# BRAINNEO.net
KiCad netlist of a schematic drawn in EAGLE
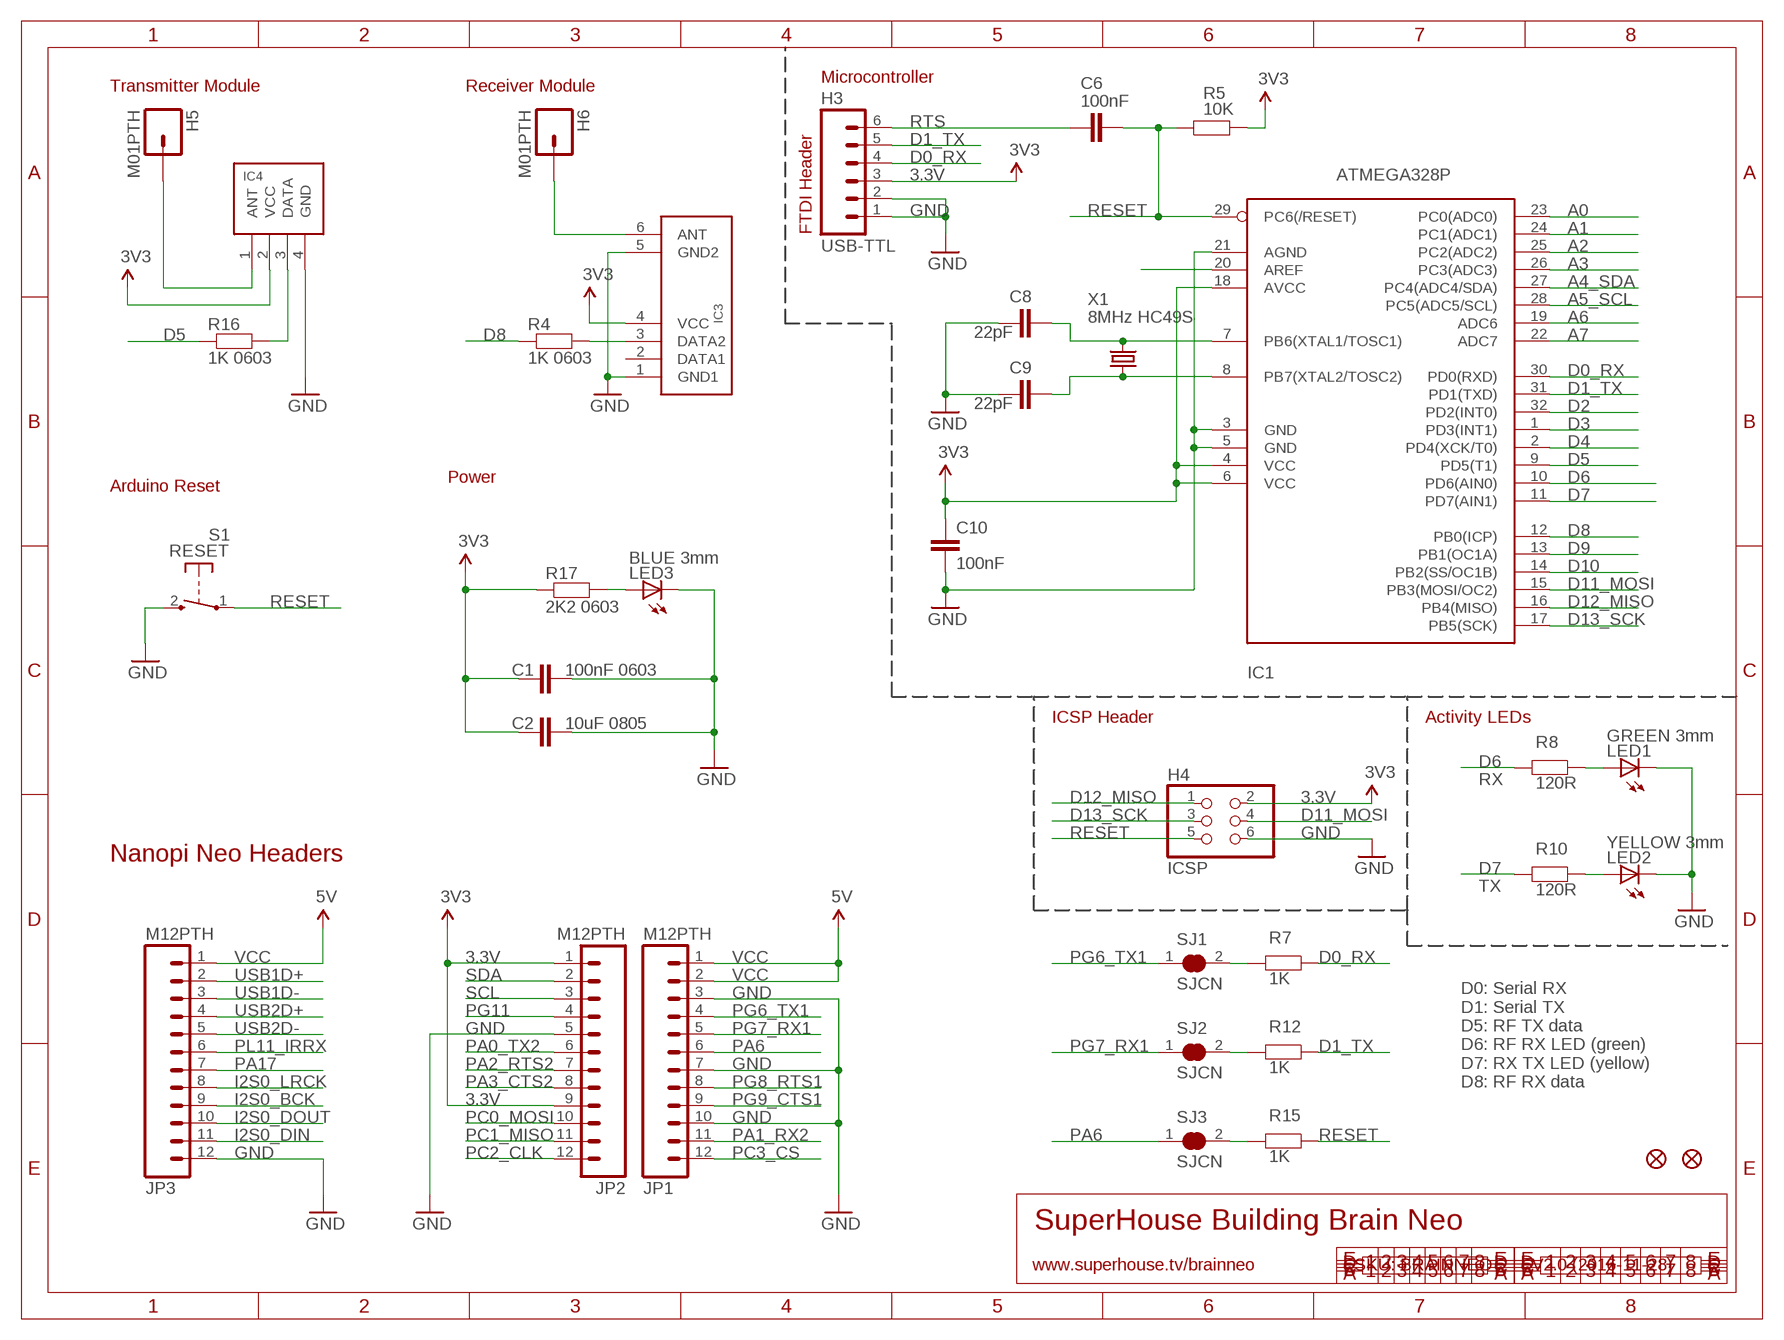
[diagram p0: schematic, sheet 1]

(export (version "E")
  (design (tool "Eeschema 10.0.6"))
  (components
    (comp (ref "C1")
      (value "100nF 0603")
      (footprint "eagle-import:0603")
      (libsource (lib "eagle-import") (part "CAP0603"))
    )
    (comp (ref "C2")
      (value "10uF 0805")
      (footprint "eagle-import:C0805")
      (libsource (lib "eagle-import") (part "C-EUC0805"))
    )
    (comp (ref "C6")
      (value "100nF")
      (footprint "eagle-import:0603")
      (libsource (lib "eagle-import") (part "freetronics-master-v1.1_CAP0603"))
    )
    (comp (ref "C8")
      (value "22pF")
      (footprint "eagle-import:0603")
      (libsource (lib "eagle-import") (part "freetronics-master-v1.1_CAP0603"))
    )
    (comp (ref "C9")
      (value "22pF")
      (footprint "eagle-import:0603")
      (libsource (lib "eagle-import") (part "freetronics-master-v1.1_CAP0603"))
    )
    (comp (ref "C10")
      (value "100nF")
      (footprint "eagle-import:0603")
      (libsource (lib "eagle-import") (part "freetronics-master-v1.1_CAP0603"))
    )
    (comp (ref "H3")
      (value "USB-TTL")
      (footprint "eagle-import:1X06")
      (libsource (lib "eagle-import") (part "M06SIP"))
    )
    (comp (ref "H4")
      (value "ICSP")
      (footprint "eagle-import:2X03")
      (libsource (lib "eagle-import") (part "PINHD-2X3"))
    )
    (comp (ref "H5")
      (value "M01PTH")
      (footprint "eagle-import:1X01")
      (libsource (lib "eagle-import") (part "M01PTH"))
    )
    (comp (ref "H6")
      (value "M01PTH")
      (footprint "eagle-import:1X01")
      (libsource (lib "eagle-import") (part "M01PTH"))
    )
    (comp (ref "IC1")
      (value "ATMEGA328P")
      (footprint "eagle-import:TQFP32-08")
      (libsource (lib "eagle-import") (part "AVR-MEGA8-AI"))
    )
    (comp (ref "IC3")
      (value "RXB1")
      (footprint "eagle-import:RX-B1-SHORT-FLAT")
      (libsource (lib "eagle-import") (part "RXB1SHORTFLAT"))
    )
    (comp (ref "IC4")
      (value "TX-C1FLAT")
      (footprint "eagle-import:TX-C1-FLAT")
      (libsource (lib "eagle-import") (part "TX-C1FLAT"))
    )
    (comp (ref "JP1")
      (value "M12PTH")
      (footprint "eagle-import:1X12")
      (libsource (lib "eagle-import") (part "M12PTH"))
    )
    (comp (ref "JP2")
      (value "M12PTH")
      (footprint "eagle-import:1X12")
      (libsource (lib "eagle-import") (part "M12PTH"))
    )
    (comp (ref "JP3")
      (value "M12PTH")
      (footprint "eagle-import:1X12")
      (libsource (lib "eagle-import") (part "M12PTH"))
    )
    (comp (ref "LED1")
      (value "GREEN 3mm")
      (footprint "eagle-import:LED3MM")
      (libsource (lib "eagle-import") (part "LED3MM"))
    )
    (comp (ref "LED2")
      (value "YELLOW 3mm")
      (footprint "eagle-import:LED3MM")
      (libsource (lib "eagle-import") (part "LED3MM"))
    )
    (comp (ref "LED3")
      (value "BLUE 3mm")
      (footprint "eagle-import:LED3MM")
      (libsource (lib "eagle-import") (part "LED3MM"))
    )
    (comp (ref "R4")
      (value "1K 0603")
      (footprint "eagle-import:0603")
      (libsource (lib "eagle-import") (part "RESISTOR0603"))
    )
    (comp (ref "R5")
      (value "10K")
      (footprint "eagle-import:0603")
      (libsource (lib "eagle-import") (part "freetronics-master-v1.1_RESISTOR0603"))
    )
    (comp (ref "R7")
      (value "1K")
      (footprint "eagle-import:0603")
      (libsource (lib "eagle-import") (part "freetronics-master-v1.1_RESISTOR0603"))
    )
    (comp (ref "R8")
      (value "120R")
      (footprint "eagle-import:0603")
      (libsource (lib "eagle-import") (part "freetronics-master-v1.1_RESISTOR0603"))
    )
    (comp (ref "R10")
      (value "120R")
      (footprint "eagle-import:0603")
      (libsource (lib "eagle-import") (part "freetronics-master-v1.1_RESISTOR0603"))
    )
    (comp (ref "R12")
      (value "1K")
      (footprint "eagle-import:0603")
      (libsource (lib "eagle-import") (part "freetronics-master-v1.1_RESISTOR0603"))
    )
    (comp (ref "R15")
      (value "1K")
      (footprint "eagle-import:0603")
      (libsource (lib "eagle-import") (part "freetronics-master-v1.1_RESISTOR0603"))
    )
    (comp (ref "R16")
      (value "1K 0603")
      (footprint "eagle-import:0603")
      (libsource (lib "eagle-import") (part "RESISTOR0603"))
    )
    (comp (ref "R17")
      (value "2K2 0603")
      (footprint "eagle-import:0603")
      (libsource (lib "eagle-import") (part "RESISTOR0603"))
    )
    (comp (ref "S1")
      (value "RESET")
      (footprint "eagle-import:TACTILE_SWITCH_SMD_2PIN_TINY")
      (libsource (lib "eagle-import") (part "TAC_SWITCH_2PIN"))
    )
    (comp (ref "SJ1")
      (value "SJCN")
      (footprint "eagle-import:SJC")
      (libsource (lib "eagle-import") (part "SJCN"))
    )
    (comp (ref "SJ2")
      (value "SJCN")
      (footprint "eagle-import:SJC")
      (libsource (lib "eagle-import") (part "SJCN"))
    )
    (comp (ref "SJ3")
      (value "SJCN")
      (footprint "eagle-import:SJC")
      (libsource (lib "eagle-import") (part "SJCN"))
    )
    (comp (ref "U$5")
      (value "FIDUCIAL1X2.5")
      (footprint "eagle-import:FIDUCIAL-1X2.5")
      (libsource (lib "eagle-import") (part "FIDUCIAL1X2.5"))
    )
    (comp (ref "U$6")
      (value "FIDUCIAL1X2.5")
      (footprint "eagle-import:FIDUCIAL-1X2.5")
      (libsource (lib "eagle-import") (part "FIDUCIAL1X2.5"))
    )
    (comp (ref "X1")
      (value "8MHz HC49S")
      (footprint "eagle-import:HC49U-V")
      (libsource (lib "eagle-import") (part "CRYSTALHC49UV"))
    )
  )
  (nets
    (net (code "1") (name "/A0") (class "Default")
      (node (ref "IC1") (pin "23") (pinfunction "PC0(ADC0)_23") (pintype "bidirectional"))
    )
    (net (code "2") (name "/A1") (class "Default")
      (node (ref "IC1") (pin "24") (pinfunction "PC1(ADC1)_24") (pintype "bidirectional"))
    )
    (net (code "3") (name "/A2") (class "Default")
      (node (ref "IC1") (pin "25") (pinfunction "PC2(ADC2)_25") (pintype "bidirectional"))
    )
    (net (code "4") (name "/A3") (class "Default")
      (node (ref "IC1") (pin "26") (pinfunction "PC3(ADC3)_26") (pintype "bidirectional"))
    )
    (net (code "5") (name "/A4_SDA") (class "Default")
      (node (ref "IC1") (pin "27") (pinfunction "PC4(ADC4/SDA)_27") (pintype "bidirectional"))
    )
    (net (code "6") (name "/A5_SCL") (class "Default")
      (node (ref "IC1") (pin "28") (pinfunction "PC5(ADC5/SCL)_28") (pintype "bidirectional"))
    )
    (net (code "7") (name "/A6") (class "Default")
      (node (ref "IC1") (pin "19") (pinfunction "ADC6_19") (pintype "bidirectional"))
    )
    (net (code "8") (name "/A7") (class "Default")
      (node (ref "IC1") (pin "22") (pinfunction "ADC7_22") (pintype "bidirectional"))
    )
    (net (code "9") (name "/D0_RX") (class "Default")
      (node (ref "H3") (pin "4") (pinfunction "4_4") (pintype "passive"))
      (node (ref "IC1") (pin "30") (pinfunction "PD0(RXD)_30") (pintype "bidirectional"))
      (node (ref "R7") (pin "1") (pinfunction "1_1") (pintype "passive"))
    )
    (net (code "10") (name "/D1_TX") (class "Default")
      (node (ref "H3") (pin "5") (pinfunction "5_5") (pintype "passive"))
      (node (ref "IC1") (pin "31") (pinfunction "PD1(TXD)_31") (pintype "bidirectional"))
      (node (ref "R12") (pin "1") (pinfunction "1_1") (pintype "passive"))
    )
    (net (code "11") (name "/D2") (class "Default")
      (node (ref "IC1") (pin "32") (pinfunction "PD2(INT0)_32") (pintype "bidirectional"))
    )
    (net (code "12") (name "/D3") (class "Default")
      (node (ref "IC1") (pin "1") (pinfunction "PD3(INT1)_1") (pintype "bidirectional"))
    )
    (net (code "13") (name "/D4") (class "Default")
      (node (ref "IC1") (pin "2") (pinfunction "PD4(XCK/T0)_2") (pintype "bidirectional"))
    )
    (net (code "14") (name "/D5") (class "Default")
      (node (ref "IC1") (pin "9") (pinfunction "PD5(T1)_9") (pintype "bidirectional"))
      (node (ref "R16") (pin "1") (pinfunction "1_1") (pintype "passive"))
    )
    (net (code "15") (name "/D6") (class "Default")
      (node (ref "IC1") (pin "10") (pinfunction "PD6(AIN0)_10") (pintype "bidirectional"))
      (node (ref "R8") (pin "2") (pinfunction "2_2") (pintype "passive"))
    )
    (net (code "16") (name "/D7") (class "Default")
      (node (ref "IC1") (pin "11") (pinfunction "PD7(AIN1)_11") (pintype "bidirectional"))
      (node (ref "R10") (pin "2") (pinfunction "2_2") (pintype "passive"))
    )
    (net (code "17") (name "/D8") (class "Default")
      (node (ref "IC1") (pin "12") (pinfunction "PB0(ICP)_12") (pintype "bidirectional"))
      (node (ref "R4") (pin "1") (pinfunction "1_1") (pintype "passive"))
    )
    (net (code "18") (name "/D9") (class "Default")
      (node (ref "IC1") (pin "13") (pinfunction "PB1(OC1A)_13") (pintype "bidirectional"))
    )
    (net (code "19") (name "/D10") (class "Default")
      (node (ref "IC1") (pin "14") (pinfunction "PB2(SS/OC1B)_14") (pintype "bidirectional"))
    )
    (net (code "20") (name "/D11_MOSI") (class "Default")
      (node (ref "H4") (pin "4") (pinfunction "4_4") (pintype "passive"))
      (node (ref "IC1") (pin "15") (pinfunction "PB3(MOSI/OC2)_15") (pintype "bidirectional"))
    )
    (net (code "21") (name "/D12_MISO") (class "Default")
      (node (ref "H4") (pin "1") (pinfunction "1_1") (pintype "passive"))
      (node (ref "IC1") (pin "16") (pinfunction "PB4(MISO)_16") (pintype "bidirectional"))
    )
    (net (code "22") (name "/D13_SCK") (class "Default")
      (node (ref "H4") (pin "3") (pinfunction "3_3") (pintype "passive"))
      (node (ref "IC1") (pin "17") (pinfunction "PB5(SCK)_17") (pintype "bidirectional"))
    )
    (net (code "23") (name "/I2S0_BCK") (class "Default")
      (node (ref "JP3") (pin "9") (pinfunction "9_9") (pintype "passive"))
    )
    (net (code "24") (name "/I2S0_DIN") (class "Default")
      (node (ref "JP3") (pin "11") (pinfunction "11_11") (pintype "passive"))
    )
    (net (code "25") (name "/I2S0_DOUT") (class "Default")
      (node (ref "JP3") (pin "10") (pinfunction "10_10") (pintype "passive"))
    )
    (net (code "26") (name "/I2S0_LRCK") (class "Default")
      (node (ref "JP3") (pin "8") (pinfunction "8_8") (pintype "passive"))
    )
    (net (code "27") (name "/PA0_TX2") (class "Default")
      (node (ref "JP2") (pin "6") (pinfunction "6_6") (pintype "passive"))
    )
    (net (code "28") (name "/PA1_RX2") (class "Default")
      (node (ref "JP1") (pin "11") (pinfunction "11_11") (pintype "passive"))
    )
    (net (code "29") (name "/PA2_RTS2") (class "Default")
      (node (ref "JP2") (pin "7") (pinfunction "7_7") (pintype "passive"))
    )
    (net (code "30") (name "/PA3_CTS2") (class "Default")
      (node (ref "JP2") (pin "8") (pinfunction "8_8") (pintype "passive"))
    )
    (net (code "31") (name "/PA6") (class "Default")
      (node (ref "JP1") (pin "6") (pinfunction "6_6") (pintype "passive"))
      (node (ref "SJ3") (pin "1") (pinfunction "1_1") (pintype "passive"))
    )
    (net (code "32") (name "/PA17") (class "Default")
      (node (ref "JP3") (pin "7") (pinfunction "7_7") (pintype "passive"))
    )
    (net (code "33") (name "/PC0_MOSI") (class "Default")
      (node (ref "JP2") (pin "10") (pinfunction "10_10") (pintype "passive"))
    )
    (net (code "34") (name "/PC1_MISO") (class "Default")
      (node (ref "JP2") (pin "11") (pinfunction "11_11") (pintype "passive"))
    )
    (net (code "35") (name "/PC2_CLK") (class "Default")
      (node (ref "JP2") (pin "12") (pinfunction "12_12") (pintype "passive"))
    )
    (net (code "36") (name "/PC3_CS") (class "Default")
      (node (ref "JP1") (pin "12") (pinfunction "12_12") (pintype "passive"))
    )
    (net (code "37") (name "/PG6_TX1") (class "Default")
      (node (ref "JP1") (pin "4") (pinfunction "4_4") (pintype "passive"))
      (node (ref "SJ1") (pin "1") (pinfunction "1_1") (pintype "passive"))
    )
    (net (code "38") (name "/PG7_RX1") (class "Default")
      (node (ref "JP1") (pin "5") (pinfunction "5_5") (pintype "passive"))
      (node (ref "SJ2") (pin "1") (pinfunction "1_1") (pintype "passive"))
    )
    (net (code "39") (name "/PG8_RTS1") (class "Default")
      (node (ref "JP1") (pin "8") (pinfunction "8_8") (pintype "passive"))
    )
    (net (code "40") (name "/PG9_CTS1") (class "Default")
      (node (ref "JP1") (pin "9") (pinfunction "9_9") (pintype "passive"))
    )
    (net (code "41") (name "/PG11") (class "Default")
      (node (ref "JP2") (pin "4") (pinfunction "4_4") (pintype "passive"))
    )
    (net (code "42") (name "/PL11_IRRX") (class "Default")
      (node (ref "JP3") (pin "6") (pinfunction "6_6") (pintype "passive"))
    )
    (net (code "43") (name "/RESET") (class "Default")
      (node (ref "C6") (pin "2") (pinfunction "2_2") (pintype "passive"))
      (node (ref "H4") (pin "5") (pinfunction "5_5") (pintype "passive"))
      (node (ref "IC1") (pin "29") (pinfunction "PC6(/RESET)_29") (pintype "bidirectional"))
      (node (ref "R15") (pin "1") (pinfunction "1_1") (pintype "passive"))
      (node (ref "R5") (pin "1") (pinfunction "1_1") (pintype "passive"))
      (node (ref "S1") (pin "1") (pinfunction "P_1") (pintype "passive"))
    )
    (net (code "44") (name "/RTS") (class "Default")
      (node (ref "C6") (pin "1") (pinfunction "1_1") (pintype "passive"))
      (node (ref "H3") (pin "6") (pinfunction "6_6") (pintype "passive"))
    )
    (net (code "45") (name "/SCL") (class "Default")
      (node (ref "JP2") (pin "3") (pinfunction "3_3") (pintype "passive"))
    )
    (net (code "46") (name "/SDA") (class "Default")
      (node (ref "JP2") (pin "2") (pinfunction "2_2") (pintype "passive"))
    )
    (net (code "47") (name "/USB1D+") (class "Default")
      (node (ref "JP3") (pin "2") (pinfunction "2_2") (pintype "passive"))
    )
    (net (code "48") (name "/USB1D-") (class "Default")
      (node (ref "JP3") (pin "3") (pinfunction "3_3") (pintype "passive"))
    )
    (net (code "49") (name "/USB2D+") (class "Default")
      (node (ref "JP3") (pin "4") (pinfunction "4_4") (pintype "passive"))
    )
    (net (code "50") (name "/USB2D-") (class "Default")
      (node (ref "JP3") (pin "5") (pinfunction "5_5") (pintype "passive"))
    )
    (net (code "51") (name "3V3") (class "Default")
      (node (ref "C1") (pin "1") (pinfunction "1_1") (pintype "passive"))
      (node (ref "C10") (pin "1") (pinfunction "1_1") (pintype "passive"))
      (node (ref "C2") (pin "2") (pinfunction "2_2") (pintype "passive"))
      (node (ref "H3") (pin "3") (pinfunction "3_3") (pintype "passive"))
      (node (ref "H4") (pin "2") (pinfunction "2_2") (pintype "passive"))
      (node (ref "IC1") (pin "18") (pinfunction "AVCC_18") (pintype "bidirectional"))
      (node (ref "IC1") (pin "4") (pinfunction "VCC_4") (pintype "bidirectional"))
      (node (ref "IC1") (pin "6") (pinfunction "VCC_6") (pintype "bidirectional"))
      (node (ref "IC3") (pin "4") (pinfunction "VCC_4") (pintype "bidirectional"))
      (node (ref "IC4") (pin "2") (pinfunction "VCC_2") (pintype "power_in"))
      (node (ref "JP2") (pin "1") (pinfunction "1_1") (pintype "passive"))
      (node (ref "JP2") (pin "9") (pinfunction "9_9") (pintype "passive"))
      (node (ref "R17") (pin "1") (pinfunction "1_1") (pintype "passive"))
      (node (ref "R5") (pin "2") (pinfunction "2_2") (pintype "passive"))
    )
    (net (code "52") (name "5V") (class "Default")
      (node (ref "JP1") (pin "1") (pinfunction "1_1") (pintype "passive"))
      (node (ref "JP1") (pin "2") (pinfunction "2_2") (pintype "passive"))
      (node (ref "JP3") (pin "1") (pinfunction "1_1") (pintype "passive"))
    )
    (net (code "53") (name "GND") (class "Default")
      (node (ref "C1") (pin "2") (pinfunction "2_2") (pintype "passive"))
      (node (ref "C10") (pin "2") (pinfunction "2_2") (pintype "passive"))
      (node (ref "C2") (pin "1") (pinfunction "1_1") (pintype "passive"))
      (node (ref "C8") (pin "1") (pinfunction "1_1") (pintype "passive"))
      (node (ref "C9") (pin "1") (pinfunction "1_1") (pintype "passive"))
      (node (ref "H3") (pin "1") (pinfunction "1_1") (pintype "passive"))
      (node (ref "H3") (pin "2") (pinfunction "2_2") (pintype "passive"))
      (node (ref "H4") (pin "6") (pinfunction "6_6") (pintype "passive"))
      (node (ref "IC1") (pin "21") (pinfunction "AGND_21") (pintype "bidirectional"))
      (node (ref "IC1") (pin "3") (pinfunction "GND_3") (pintype "bidirectional"))
      (node (ref "IC1") (pin "5") (pinfunction "GND_5") (pintype "bidirectional"))
      (node (ref "IC3") (pin "1") (pinfunction "GND1_1") (pintype "bidirectional"))
      (node (ref "IC3") (pin "5") (pinfunction "GND2_5") (pintype "bidirectional"))
      (node (ref "IC4") (pin "4") (pinfunction "GND_4") (pintype "power_in"))
      (node (ref "JP1") (pin "10") (pinfunction "10_10") (pintype "passive"))
      (node (ref "JP1") (pin "3") (pinfunction "3_3") (pintype "passive"))
      (node (ref "JP1") (pin "7") (pinfunction "7_7") (pintype "passive"))
      (node (ref "JP2") (pin "5") (pinfunction "5_5") (pintype "passive"))
      (node (ref "JP3") (pin "12") (pinfunction "12_12") (pintype "passive"))
      (node (ref "LED1") (pin "K") (pinfunction "C_K") (pintype "passive"))
      (node (ref "LED2") (pin "K") (pinfunction "C_K") (pintype "passive"))
      (node (ref "LED3") (pin "K") (pinfunction "C_K") (pintype "passive"))
      (node (ref "S1") (pin "2") (pinfunction "S_2") (pintype "passive"))
    )
    (net (code "54") (name "Net-(IC1-PB6(XTAL1{slash}TOSC1))") (class "Default")
      (node (ref "C8") (pin "2") (pinfunction "2_2") (pintype "passive"))
      (node (ref "IC1") (pin "7") (pinfunction "PB6(XTAL1/TOSC1)_7") (pintype "bidirectional"))
      (node (ref "X1") (pin "2") (pinfunction "2_2") (pintype "passive"))
    )
    (net (code "55") (name "Net-(IC1-PB7(XTAL2{slash}TOSC2))") (class "Default")
      (node (ref "C9") (pin "2") (pinfunction "2_2") (pintype "passive"))
      (node (ref "IC1") (pin "8") (pinfunction "PB7(XTAL2/TOSC2)_8") (pintype "bidirectional"))
      (node (ref "X1") (pin "1") (pinfunction "1_1") (pintype "passive"))
    )
    (net (code "56") (name "Net-(IC3-ANT)") (class "Default")
      (node (ref "H6") (pin "1") (pinfunction "1_1") (pintype "passive"))
      (node (ref "IC3") (pin "6") (pinfunction "ANT_6") (pintype "bidirectional"))
    )
    (net (code "57") (name "Net-(IC3-DATA2)") (class "Default")
      (node (ref "IC3") (pin "3") (pinfunction "DATA2_3") (pintype "bidirectional"))
      (node (ref "R4") (pin "2") (pinfunction "2_2") (pintype "passive"))
    )
    (net (code "58") (name "Net-(IC4-ANT)") (class "Default")
      (node (ref "H5") (pin "1") (pinfunction "1_1") (pintype "passive"))
      (node (ref "IC4") (pin "1") (pinfunction "ANT_1") (pintype "output"))
    )
    (net (code "59") (name "Net-(IC4-DATA)") (class "Default")
      (node (ref "IC4") (pin "3") (pinfunction "DATA_3") (pintype "input"))
      (node (ref "R16") (pin "2") (pinfunction "2_2") (pintype "passive"))
    )
    (net (code "60") (name "Net-(LED1-PadA)") (class "Default")
      (node (ref "LED1") (pin "A") (pinfunction "A_A") (pintype "passive"))
      (node (ref "R8") (pin "1") (pinfunction "1_1") (pintype "passive"))
    )
    (net (code "61") (name "Net-(LED2-PadA)") (class "Default")
      (node (ref "LED2") (pin "A") (pinfunction "A_A") (pintype "passive"))
      (node (ref "R10") (pin "1") (pinfunction "1_1") (pintype "passive"))
    )
    (net (code "62") (name "Net-(LED3-PadA)") (class "Default")
      (node (ref "LED3") (pin "A") (pinfunction "A_A") (pintype "passive"))
      (node (ref "R17") (pin "2") (pinfunction "2_2") (pintype "passive"))
    )
    (net (code "63") (name "Net-(R7-Pad2)") (class "Default")
      (node (ref "R7") (pin "2") (pinfunction "2_2") (pintype "passive"))
      (node (ref "SJ1") (pin "2") (pinfunction "2_2") (pintype "passive"))
    )
    (net (code "64") (name "Net-(R12-Pad2)") (class "Default")
      (node (ref "R12") (pin "2") (pinfunction "2_2") (pintype "passive"))
      (node (ref "SJ2") (pin "2") (pinfunction "2_2") (pintype "passive"))
    )
    (net (code "65") (name "Net-(R15-Pad2)") (class "Default")
      (node (ref "R15") (pin "2") (pinfunction "2_2") (pintype "passive"))
      (node (ref "SJ3") (pin "2") (pinfunction "2_2") (pintype "passive"))
    )
    (net (code "66") (name "unconnected-(IC1-AREF-Pad20)") (class "Default")
      (node (ref "IC1") (pin "20") (pinfunction "AREF_20") (pintype "bidirectional"))
    )
    (net (code "67") (name "unconnected-(IC3-DATA1-Pad2)") (class "Default")
      (node (ref "IC3") (pin "2") (pinfunction "DATA1_2") (pintype "bidirectional"))
    )
  )
)
